# working.net
KiCad netlist of a schematic drawn in EAGLE
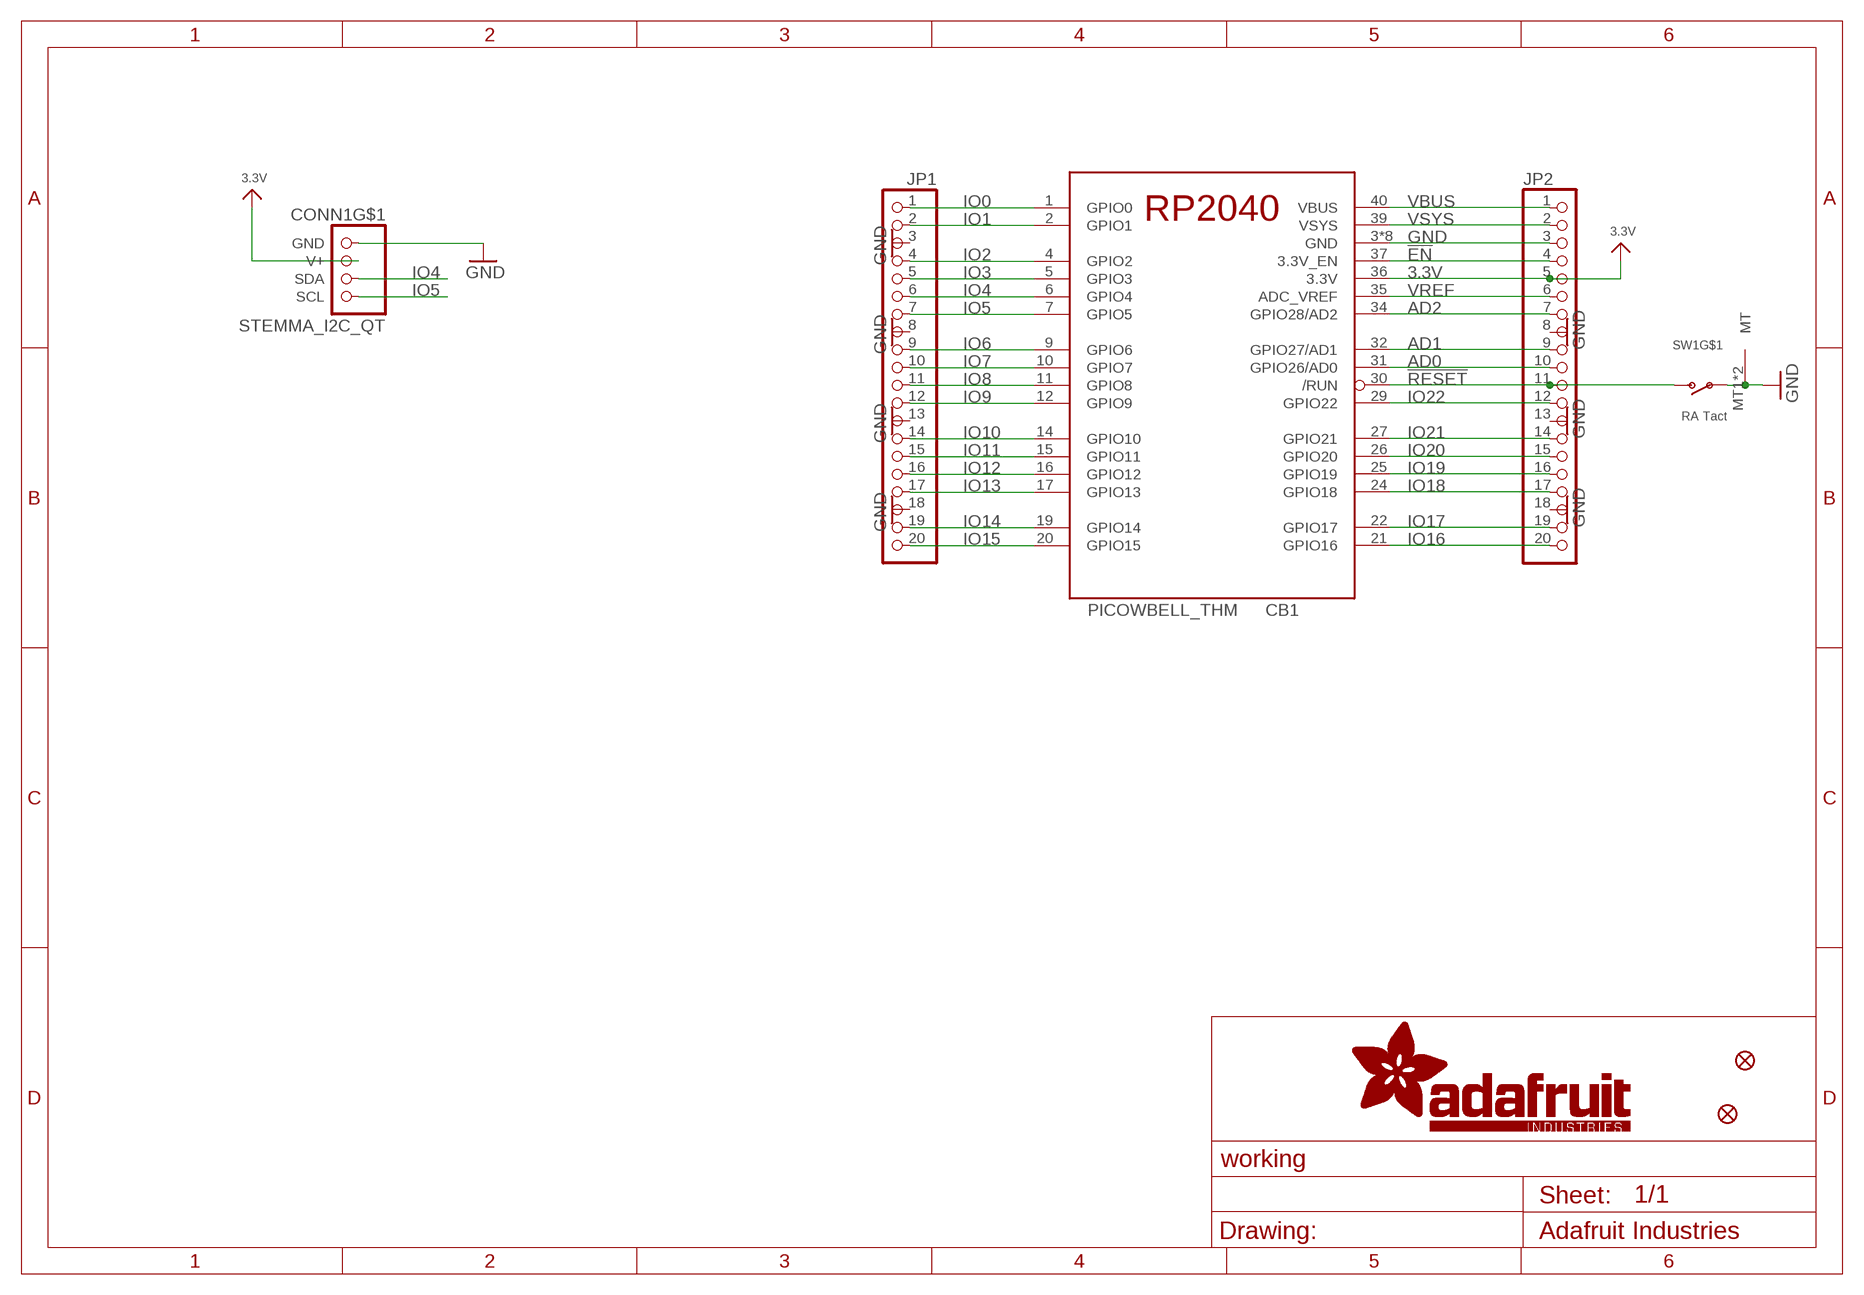
[diagram p0: schematic, sheet 1]

(export (version "E")
  (design (tool "Eeschema 10.0.6"))
  (components
    (comp (ref "CB1")
      (value "PICOWBELL_THM")
      (footprint "eagle-import:PICOWBELL")
      (libsource (lib "eagle-import") (part "PICOWBELL_THM"))
    )
    (comp (ref "CONN1")
      (value "STEMMA_I2C_QT")
      (footprint "eagle-import:JST_SH4")
      (libsource (lib "eagle-import") (part "STEMMA_I2C_QT"))
    )
    (comp (ref "FID1")
      (value "FIDUCIAL_1MM")
      (footprint "eagle-import:FIDUCIAL_1MM")
      (libsource (lib "eagle-import") (part "FIDUCIAL_1MM"))
    )
    (comp (ref "FID2")
      (value "FIDUCIAL_1MM")
      (footprint "eagle-import:FIDUCIAL_1MM")
      (libsource (lib "eagle-import") (part "FIDUCIAL_1MM"))
    )
    (comp (ref "JP1")
      (value "HEADER-1X20_70MIL")
      (footprint "eagle-import:1X20_ROUND_70MIL")
      (libsource (lib "eagle-import") (part "HEADER-1X20_70MIL"))
    )
    (comp (ref "JP2")
      (value "HEADER-1X20_70MIL")
      (footprint "eagle-import:1X20_ROUND_70MIL")
      (libsource (lib "eagle-import") (part "HEADER-1X20_70MIL"))
    )
    (comp (ref "SW1")
      (value "RA Tact")
      (footprint "eagle-import:SPST_TACTILE_RA")
      (libsource (lib "eagle-import") (part "SWITCH_SPST_MNT_TACT_RA"))
    )
  )
  (nets
    (net (code "1") (name "/AD0") (class "Default")
      (node (ref "CB1") (pin "31") (pinfunction "GPIO26/AD0_31") (pintype "bidirectional"))
      (node (ref "JP2") (pin "10") (pinfunction "10_10") (pintype "passive"))
    )
    (net (code "2") (name "/AD1") (class "Default")
      (node (ref "CB1") (pin "32") (pinfunction "GPIO27/AD1_32") (pintype "bidirectional"))
      (node (ref "JP2") (pin "9") (pinfunction "9_9") (pintype "passive"))
    )
    (net (code "3") (name "/AD2") (class "Default")
      (node (ref "CB1") (pin "34") (pinfunction "GPIO28/AD2_34") (pintype "bidirectional"))
      (node (ref "JP2") (pin "7") (pinfunction "7_7") (pintype "passive"))
    )
    (net (code "4") (name "/IO0") (class "Default")
      (node (ref "CB1") (pin "1") (pinfunction "GPIO0_1") (pintype "bidirectional"))
      (node (ref "JP1") (pin "1") (pinfunction "1_1") (pintype "passive"))
    )
    (net (code "5") (name "/IO1") (class "Default")
      (node (ref "CB1") (pin "2") (pinfunction "GPIO1_2") (pintype "bidirectional"))
      (node (ref "JP1") (pin "2") (pinfunction "2_2") (pintype "passive"))
    )
    (net (code "6") (name "/IO2") (class "Default")
      (node (ref "CB1") (pin "4") (pinfunction "GPIO2_4") (pintype "bidirectional"))
      (node (ref "JP1") (pin "4") (pinfunction "4_4") (pintype "passive"))
    )
    (net (code "7") (name "/IO3") (class "Default")
      (node (ref "CB1") (pin "5") (pinfunction "GPIO3_5") (pintype "bidirectional"))
      (node (ref "JP1") (pin "5") (pinfunction "5_5") (pintype "passive"))
    )
    (net (code "8") (name "/IO4") (class "Default")
      (node (ref "CB1") (pin "6") (pinfunction "GPIO4_6") (pintype "bidirectional"))
      (node (ref "CONN1") (pin "3") (pinfunction "SDA_3") (pintype "passive"))
      (node (ref "JP1") (pin "6") (pinfunction "6_6") (pintype "passive"))
    )
    (net (code "9") (name "/IO5") (class "Default")
      (node (ref "CB1") (pin "7") (pinfunction "GPIO5_7") (pintype "bidirectional"))
      (node (ref "CONN1") (pin "4") (pinfunction "SCL_4") (pintype "passive"))
      (node (ref "JP1") (pin "7") (pinfunction "7_7") (pintype "passive"))
    )
    (net (code "10") (name "/IO6") (class "Default")
      (node (ref "CB1") (pin "9") (pinfunction "GPIO6_9") (pintype "bidirectional"))
      (node (ref "JP1") (pin "9") (pinfunction "9_9") (pintype "passive"))
    )
    (net (code "11") (name "/IO7") (class "Default")
      (node (ref "CB1") (pin "10") (pinfunction "GPIO7_10") (pintype "bidirectional"))
      (node (ref "JP1") (pin "10") (pinfunction "10_10") (pintype "passive"))
    )
    (net (code "12") (name "/IO8") (class "Default")
      (node (ref "CB1") (pin "11") (pinfunction "GPIO8_11") (pintype "bidirectional"))
      (node (ref "JP1") (pin "11") (pinfunction "11_11") (pintype "passive"))
    )
    (net (code "13") (name "/IO9") (class "Default")
      (node (ref "CB1") (pin "12") (pinfunction "GPIO9_12") (pintype "bidirectional"))
      (node (ref "JP1") (pin "12") (pinfunction "12_12") (pintype "passive"))
    )
    (net (code "14") (name "/IO10") (class "Default")
      (node (ref "CB1") (pin "14") (pinfunction "GPIO10_14") (pintype "bidirectional"))
      (node (ref "JP1") (pin "14") (pinfunction "14_14") (pintype "passive"))
    )
    (net (code "15") (name "/IO11") (class "Default")
      (node (ref "CB1") (pin "15") (pinfunction "GPIO11_15") (pintype "bidirectional"))
      (node (ref "JP1") (pin "15") (pinfunction "15_15") (pintype "passive"))
    )
    (net (code "16") (name "/IO12") (class "Default")
      (node (ref "CB1") (pin "16") (pinfunction "GPIO12_16") (pintype "bidirectional"))
      (node (ref "JP1") (pin "16") (pinfunction "16_16") (pintype "passive"))
    )
    (net (code "17") (name "/IO13") (class "Default")
      (node (ref "CB1") (pin "17") (pinfunction "GPIO13_17") (pintype "bidirectional"))
      (node (ref "JP1") (pin "17") (pinfunction "17_17") (pintype "passive"))
    )
    (net (code "18") (name "/IO14") (class "Default")
      (node (ref "CB1") (pin "19") (pinfunction "GPIO14_19") (pintype "bidirectional"))
      (node (ref "JP1") (pin "19") (pinfunction "19_19") (pintype "passive"))
    )
    (net (code "19") (name "/IO15") (class "Default")
      (node (ref "CB1") (pin "20") (pinfunction "GPIO15_20") (pintype "bidirectional"))
      (node (ref "JP1") (pin "20") (pinfunction "20_20") (pintype "passive"))
    )
    (net (code "20") (name "/IO16") (class "Default")
      (node (ref "CB1") (pin "21") (pinfunction "GPIO16_21") (pintype "bidirectional"))
      (node (ref "JP2") (pin "20") (pinfunction "20_20") (pintype "passive"))
    )
    (net (code "21") (name "/IO17") (class "Default")
      (node (ref "CB1") (pin "22") (pinfunction "GPIO17_22") (pintype "bidirectional"))
      (node (ref "JP2") (pin "19") (pinfunction "19_19") (pintype "passive"))
    )
    (net (code "22") (name "/IO18") (class "Default")
      (node (ref "CB1") (pin "24") (pinfunction "GPIO18_24") (pintype "bidirectional"))
      (node (ref "JP2") (pin "17") (pinfunction "17_17") (pintype "passive"))
    )
    (net (code "23") (name "/IO19") (class "Default")
      (node (ref "CB1") (pin "25") (pinfunction "GPIO19_25") (pintype "bidirectional"))
      (node (ref "JP2") (pin "16") (pinfunction "16_16") (pintype "passive"))
    )
    (net (code "24") (name "/IO20") (class "Default")
      (node (ref "CB1") (pin "26") (pinfunction "GPIO20_26") (pintype "bidirectional"))
      (node (ref "JP2") (pin "15") (pinfunction "15_15") (pintype "passive"))
    )
    (net (code "25") (name "/IO21") (class "Default")
      (node (ref "CB1") (pin "27") (pinfunction "GPIO21_27") (pintype "bidirectional"))
      (node (ref "JP2") (pin "14") (pinfunction "14_14") (pintype "passive"))
    )
    (net (code "26") (name "/IO22") (class "Default")
      (node (ref "CB1") (pin "29") (pinfunction "GPIO22_29") (pintype "bidirectional"))
      (node (ref "JP2") (pin "12") (pinfunction "12_12") (pintype "passive"))
    )
    (net (code "27") (name "/VBUS") (class "Default")
      (node (ref "CB1") (pin "40") (pinfunction "VBUS_40") (pintype "power_in"))
      (node (ref "JP2") (pin "1") (pinfunction "1_1") (pintype "passive"))
    )
    (net (code "28") (name "/VREF") (class "Default")
      (node (ref "CB1") (pin "35") (pinfunction "ADC_VREF_35") (pintype "passive"))
      (node (ref "JP2") (pin "6") (pinfunction "6_6") (pintype "passive"))
    )
    (net (code "29") (name "/VSYS") (class "Default")
      (node (ref "CB1") (pin "39") (pinfunction "VSYS_39") (pintype "power_in"))
      (node (ref "JP2") (pin "2") (pinfunction "2_2") (pintype "passive"))
    )
    (net (code "30") (name "/~{EN}") (class "Default")
      (node (ref "CB1") (pin "37") (pinfunction "3.3V_EN_37") (pintype "passive"))
      (node (ref "JP2") (pin "4") (pinfunction "4_4") (pintype "passive"))
    )
    (net (code "31") (name "/~{RESET}") (class "Default")
      (node (ref "CB1") (pin "30") (pinfunction "/RUN_30") (pintype "bidirectional"))
      (node (ref "JP2") (pin "11") (pinfunction "11_11") (pintype "passive"))
      (node (ref "SW1") (pin "2") (pinfunction "S_2") (pintype "passive"))
    )
    (net (code "32") (name "3.3V") (class "Default")
      (node (ref "CB1") (pin "36") (pinfunction "3.3V_36") (pintype "power_in"))
      (node (ref "CONN1") (pin "2") (pinfunction "V+_2") (pintype "passive"))
      (node (ref "JP2") (pin "5") (pinfunction "5_5") (pintype "passive"))
    )
    (net (code "33") (name "GND") (class "Default")
      (node (ref "CB1") (pin "13") (pinfunction "GND_13") (pintype "power_in"))
      (node (ref "CB1") (pin "18") (pinfunction "GND_18") (pintype "power_in"))
      (node (ref "CB1") (pin "23") (pinfunction "GND_23") (pintype "power_in"))
      (node (ref "CB1") (pin "28") (pinfunction "GND_28") (pintype "power_in"))
      (node (ref "CB1") (pin "3") (pinfunction "GND_3") (pintype "power_in"))
      (node (ref "CB1") (pin "33") (pinfunction "GND_33") (pintype "power_in"))
      (node (ref "CB1") (pin "38") (pinfunction "GND_38") (pintype "power_in"))
      (node (ref "CB1") (pin "8") (pinfunction "GND_8") (pintype "power_in"))
      (node (ref "CONN1") (pin "1") (pinfunction "GND_1") (pintype "passive"))
      (node (ref "JP1") (pin "13") (pinfunction "13_13") (pintype "passive"))
      (node (ref "JP1") (pin "18") (pinfunction "18_18") (pintype "passive"))
      (node (ref "JP1") (pin "3") (pinfunction "3_3") (pintype "passive"))
      (node (ref "JP1") (pin "8") (pinfunction "8_8") (pintype "passive"))
      (node (ref "JP2") (pin "13") (pinfunction "13_13") (pintype "passive"))
      (node (ref "JP2") (pin "18") (pinfunction "18_18") (pintype "passive"))
      (node (ref "JP2") (pin "3") (pinfunction "3_3") (pintype "passive"))
      (node (ref "JP2") (pin "8") (pinfunction "8_8") (pintype "passive"))
      (node (ref "SW1") (pin "1") (pinfunction "P_1") (pintype "passive"))
      (node (ref "SW1") (pin "MT1") (pinfunction "MT_MT1") (pintype "bidirectional"))
      (node (ref "SW1") (pin "MT2") (pinfunction "MT_MT2") (pintype "bidirectional"))
    )
  )
)
